# MagSwitchRev1_2.net
KiCad netlist of a schematic drawn in EAGLE
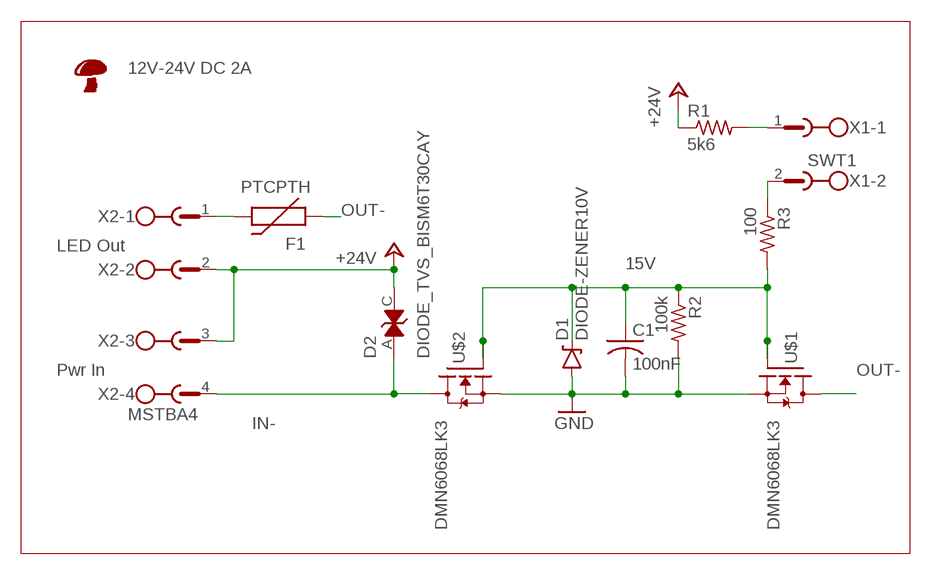
[diagram p0: schematic, sheet 1]

(export (version "E")
  (design (tool "Eeschema 10.0.6"))
  (components
    (comp (ref "C1")
      (value "100nF")
      (footprint "eagle-import:C0805")
      (libsource (lib "eagle-import") (part "C-USC0805"))
    )
    (comp (ref "D1")
      (value "DIODE-ZENER10V")
      (footprint "eagle-import:SOD-323")
      (libsource (lib "eagle-import") (part "DIODE-ZENER15V"))
    )
    (comp (ref "D2")
      (value "DIODE_TVS_BISM6T30CAY")
      (footprint "eagle-import:SMB-DIODE")
      (libsource (lib "eagle-import") (part "DIODE_TVS_BISM6T30CAY"))
    )
    (comp (ref "F1")
      (value "PTCPTH")
      (footprint "eagle-import:PTC")
      (libsource (lib "eagle-import") (part "PTCPTH"))
    )
    (comp (ref "R1")
      (value "5k6")
      (footprint "eagle-import:M0805")
      (libsource (lib "eagle-import") (part "R-US_M0805"))
    )
    (comp (ref "R2")
      (value "100k")
      (footprint "eagle-import:M0805")
      (libsource (lib "eagle-import") (part "R-US_M0805"))
    )
    (comp (ref "R3")
      (value "100")
      (footprint "eagle-import:M0805")
      (libsource (lib "eagle-import") (part "R-US_M0805"))
    )
    (comp (ref "U$1")
      (value "DMN6068LK3")
      (footprint "eagle-import:TO252")
      (libsource (lib "eagle-import") (part "DMN6068LK3"))
    )
    (comp (ref "U$2")
      (value "DMN6068LK3")
      (footprint "eagle-import:TO252")
      (libsource (lib "eagle-import") (part "DMN6068LK3"))
    )
    (comp (ref "U$4")
      (value "SHROOM5MM")
      (footprint "eagle-import:SHROOM")
      (libsource (lib "eagle-import") (part "SHROOM5MM"))
    )
    (comp (ref "X1")
      (value "SWT1")
      (footprint "eagle-import:MSTBA2")
      (fields (field (name "MF") "FARNELL") (field (name "MPN") "1757242"))
      (libsource (lib "eagle-import") (part "MSTBA2"))
    )
    (comp (ref "X2")
      (value "MSTBA4")
      (footprint "eagle-import:MSTBA4")
      (fields (field (name "MF") "FARNELL") (field (name "MPN") "1757268"))
      (libsource (lib "eagle-import") (part "MSTBA4"))
    )
  )
  (nets
    (net (code "1") (name "+24V") (class "Default")
      (node (ref "D2") (pin "C") (pinfunction "P$2_C") (pintype "bidirectional"))
      (node (ref "R1") (pin "1") (pinfunction "1_1") (pintype "passive"))
      (node (ref "X2") (pin "2") (pinfunction "1_2") (pintype "passive"))
      (node (ref "X2") (pin "3") (pinfunction "1_3") (pintype "passive"))
    )
    (net (code "2") (name "/15V") (class "Default")
      (node (ref "C1") (pin "1") (pinfunction "1_1") (pintype "passive"))
      (node (ref "D1") (pin "C") (pinfunction "C_C") (pintype "passive"))
      (node (ref "R2") (pin "1") (pinfunction "1_1") (pintype "passive"))
      (node (ref "R3") (pin "2") (pinfunction "2_2") (pintype "passive"))
      (node (ref "U$1") (pin "1") (pinfunction "G_1") (pintype "passive"))
      (node (ref "U$2") (pin "1") (pinfunction "G_1") (pintype "passive"))
    )
    (net (code "3") (name "/IN-") (class "Default")
      (node (ref "D2") (pin "A") (pinfunction "P$1_A") (pintype "bidirectional"))
      (node (ref "U$2") (pin "3") (pinfunction "D_3") (pintype "passive"))
      (node (ref "X2") (pin "4") (pinfunction "1_4") (pintype "passive"))
    )
    (net (code "4") (name "/OUT-") (class "Default")
      (node (ref "F1") (pin "P$1") (pinfunction "1_P$1") (pintype "bidirectional"))
      (node (ref "U$1") (pin "3") (pinfunction "D_3") (pintype "passive"))
    )
    (net (code "5") (name "GND") (class "Default")
      (node (ref "C1") (pin "2") (pinfunction "2_2") (pintype "passive"))
      (node (ref "D1") (pin "A") (pinfunction "A_A") (pintype "passive"))
      (node (ref "R2") (pin "2") (pinfunction "2_2") (pintype "passive"))
      (node (ref "U$1") (pin "2") (pinfunction "S_2") (pintype "passive"))
      (node (ref "U$2") (pin "2") (pinfunction "S_2") (pintype "passive"))
    )
    (net (code "6") (name "Net-(F1-2)") (class "Default")
      (node (ref "F1") (pin "P$2") (pinfunction "2_P$2") (pintype "bidirectional"))
      (node (ref "X2") (pin "1") (pinfunction "1_1") (pintype "passive"))
    )
    (net (code "7") (name "Net-(R1-Pad2)") (class "Default")
      (node (ref "R1") (pin "2") (pinfunction "2_2") (pintype "passive"))
      (node (ref "X1") (pin "1") (pinfunction "1_1") (pintype "passive"))
    )
    (net (code "8") (name "Net-(X1B-1)") (class "Default")
      (node (ref "R3") (pin "1") (pinfunction "1_1") (pintype "passive"))
      (node (ref "X1") (pin "2") (pinfunction "1_2") (pintype "passive"))
    )
  )
)
